# ti-tmds62levm-rev-b-sheet-17.net
KiCad netlist of a schematic drawn in Altium Designer
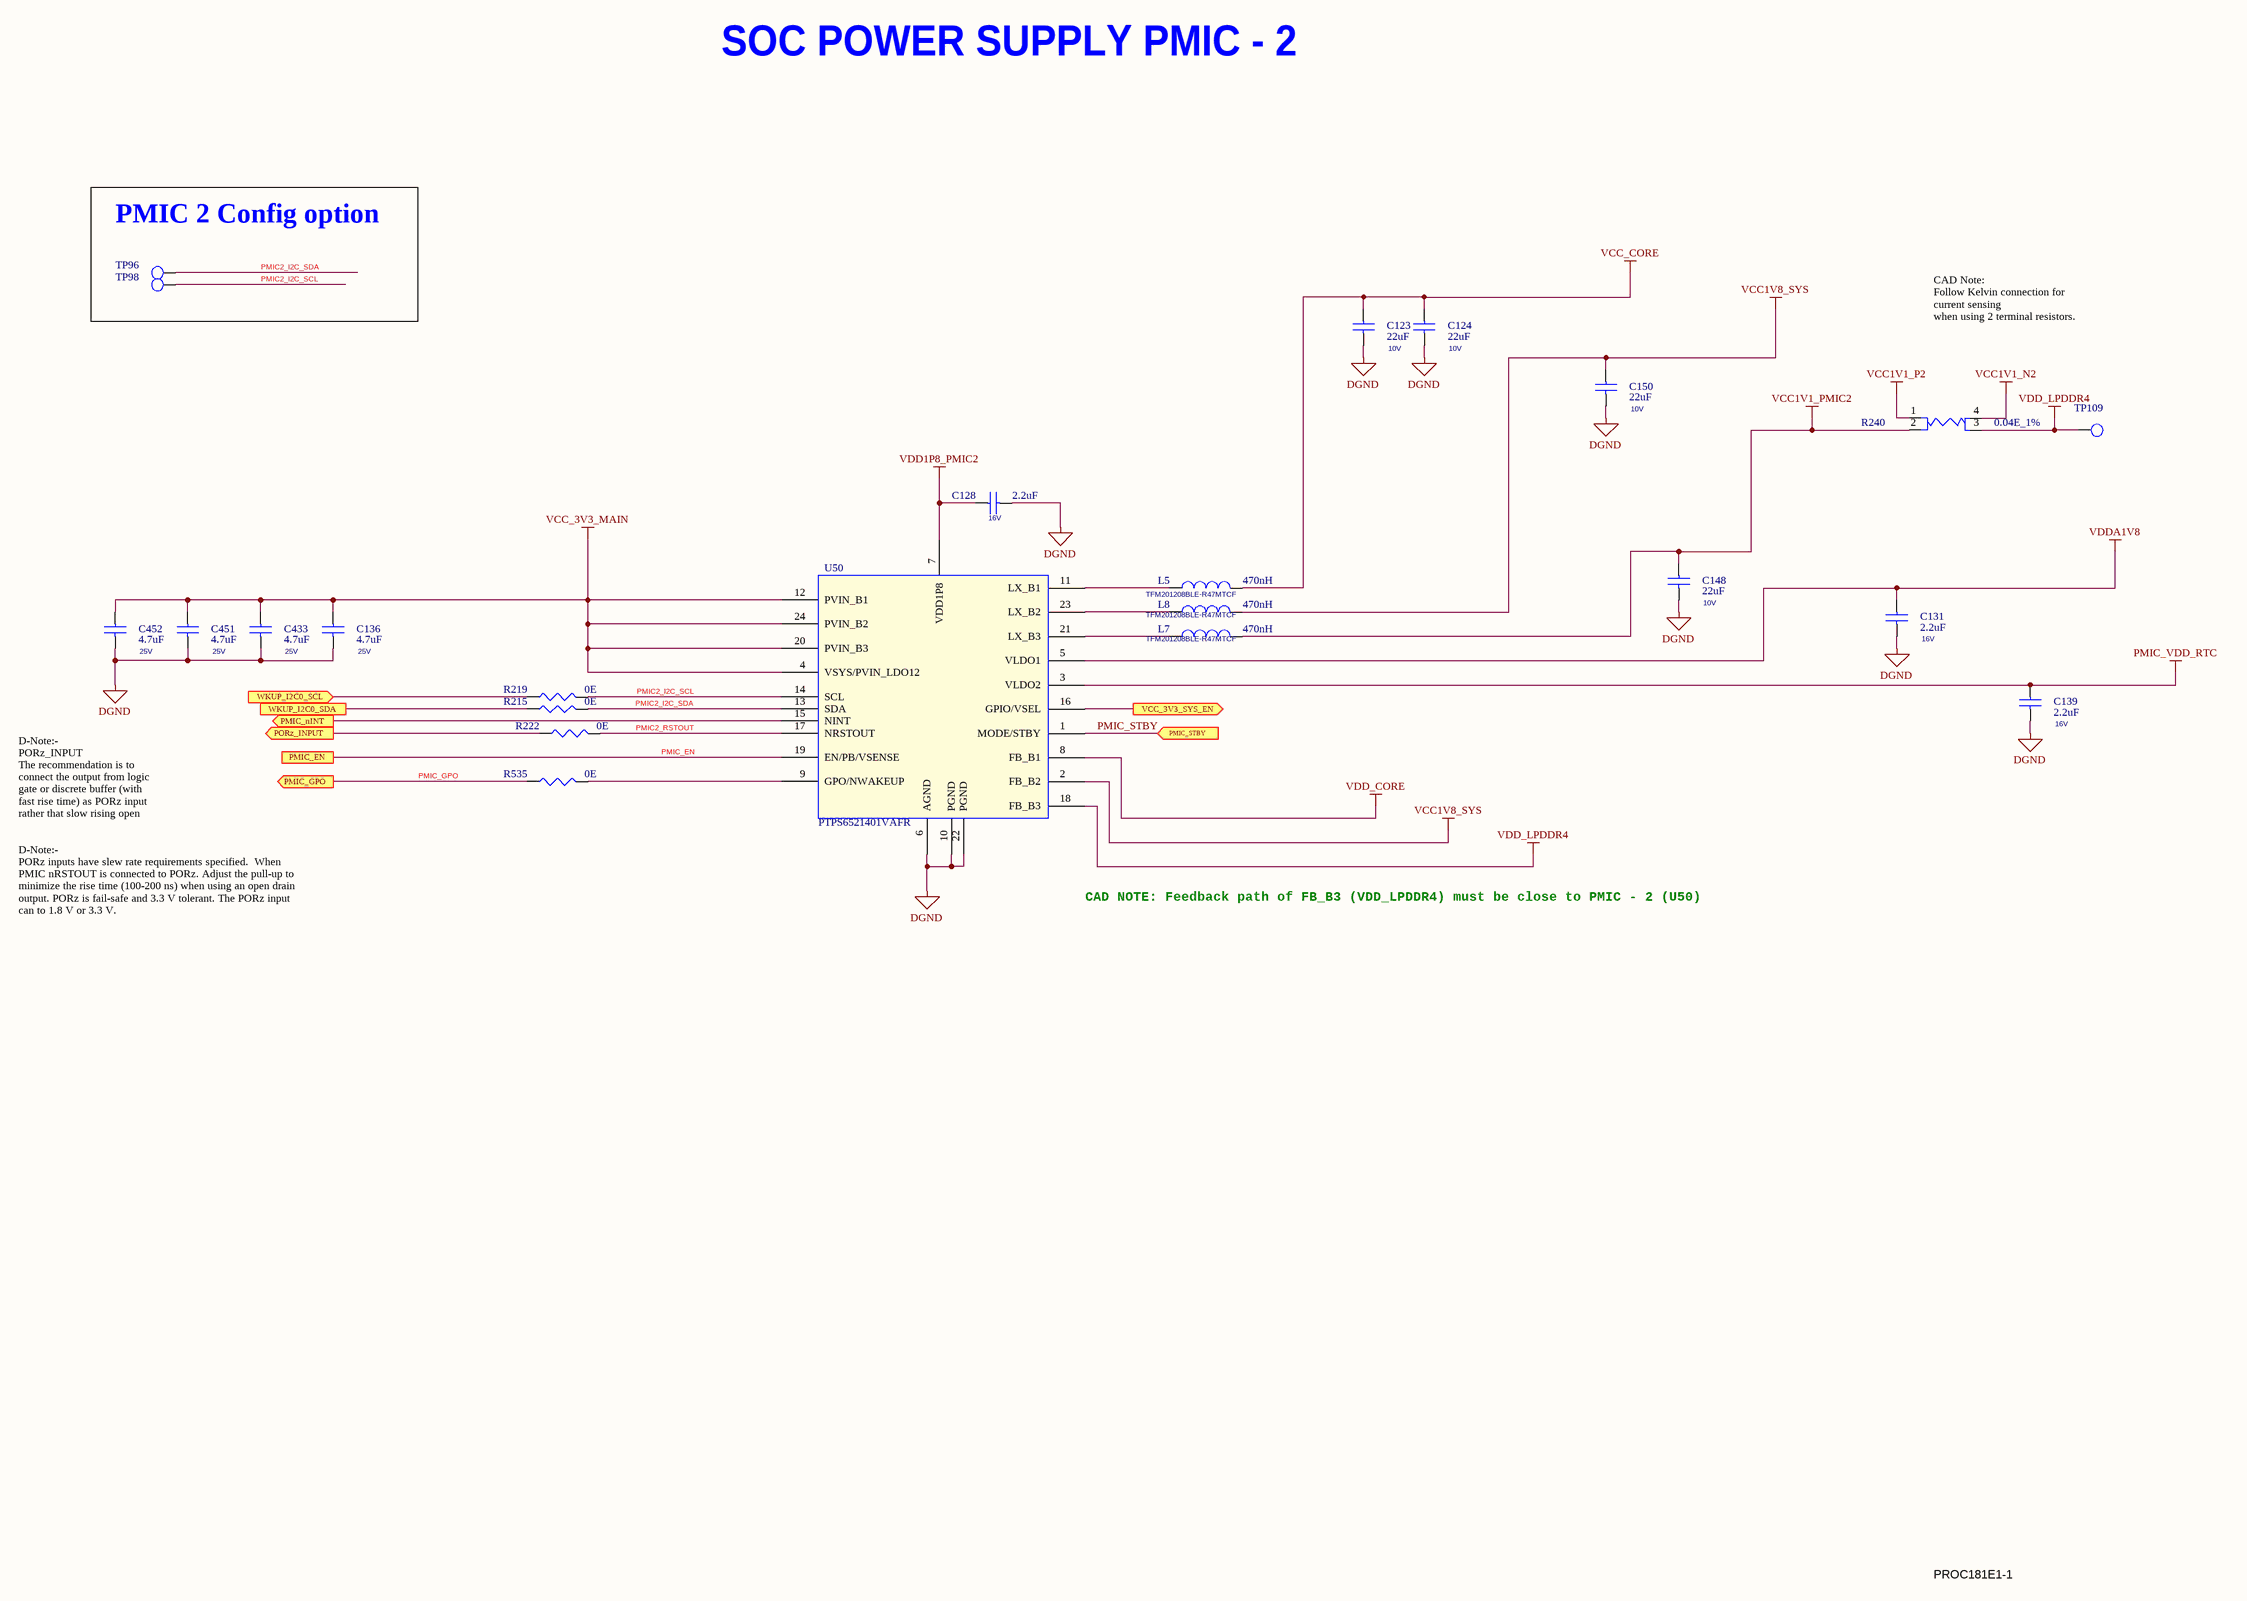
[diagram p0: ti-tmds62levm-rev-b-sheet-17.SchDoc]

(export (version "E")
  (design (tool "Eeschema 10.0.6"))
  (components
    (comp (ref "C123")
      (value "22uF")
      (footprint "CAP0805_1-5")
      (description "CAP CERAMIC 22uF 10V 20% X7R 0805")
      (fields
        (field (name "DISTRIBUTOR_PART_NUMBER") "490-GRM21BZ71A226ME15LCT-ND")
        (field (name "VOLTAGE") "10V")
        (field (name "TOLERANCE") "20%")
        (field (name "LIBRARY PATH") "Y~{:}MIS_DATABAS~{E}Librar~{y}ALTIUM_TOO~{L}SCHEMATICS_PART~{S}MS_DISCRETE_Library.schlib")
      )
      (libsource (lib "*") (part "CAP_Dup1"))
    )
    (comp (ref "C124")
      (value "22uF")
      (footprint "CAP0805_1-5")
      (description "CAP CERAMIC 22uF 10V 20% X7R 0805")
      (fields
        (field (name "MISTRAL PART NO") "120024060041-R")
        (field (name "MFR_PART_NUMBER") "GRM21BZ71A226ME15L")
        (field (name "VOLTAGE") "10V")
        (field (name "LIBRARY PATH") "Y~{:}MIS_DATABAS~{E}Librar~{y}ALTIUM_TOO~{L}SCHEMATICS_PART~{S}MS_DISCRETE_Library.schlib")
      )
      (libsource (lib "*") (part "CAP_Dup1"))
    )
    (comp (ref "C128")
      (value "2.2uF")
      (footprint "CAP0402_0-75")
      (description "CAP CERAMIC 2.2uF 16V 10% X6S 0402")
      (fields
        (field (name "DISTRIBUTOR_PART_NUMBER") "490-14595-1-ND")
        (field (name "VOLTAGE") "16V")
        (field (name "TOLERANCE") "10%")
        (field (name "LIBRARY PATH") "Y~{:}MIS_DATABAS~{E}Librar~{y}ALTIUM_TOO~{L}SCHEMATICS_PART~{S}MS_DISCRETE_Library.schlib")
      )
      (libsource (lib "*") (part "CAP_Dup1"))
    )
    (comp (ref "C131")
      (value "2.2uF")
      (footprint "CAP0402_0-75")
      (description "CAP CERAMIC 2.2uF 16V 10% X6S 0402")
      (fields
        (field (name "DISTRIBUTOR_PART_NUMBER") "490-14595-1-ND")
        (field (name "VOLTAGE") "16V")
        (field (name "TOLERANCE") "10%")
        (field (name "LIBRARY PATH") "Y~{:}MIS_DATABAS~{E}Librar~{y}ALTIUM_TOO~{L}SCHEMATICS_PART~{S}MS_DISCRETE_Library.schlib")
      )
      (libsource (lib "*") (part "CAP_Dup1"))
    )
    (comp (ref "C136")
      (value "4.7uF")
      (footprint "CAP0603_1")
      (description "CAP CERAMIC 4.7uF 25V 10% X6S 0603")
      (fields
        (field (name "DISTRIBUTOR_PART_NUMBER") "490-7199-1-ND")
        (field (name "VOLTAGE") "25V")
        (field (name "TOLERANCE") "10%")
        (field (name "LIBRARY PATH") "Y~{:}MIS_DATABAS~{E}Librar~{y}ALTIUM_TOO~{L}SCHEMATICS_PART~{S}MS_DISCRETE_Library.schlib")
      )
      (libsource (lib "*") (part "CAP_Dup1"))
    )
    (comp (ref "C139")
      (value "2.2uF")
      (footprint "CAP0402_0-75")
      (description "CAP CERAMIC 2.2uF 16V 10% X6S 0402")
      (fields
        (field (name "DISTRIBUTOR_PART_NUMBER") "490-14595-1-ND")
        (field (name "VOLTAGE") "16V")
        (field (name "TOLERANCE") "10%")
        (field (name "LIBRARY PATH") "Y~{:}MIS_DATABAS~{E}Librar~{y}ALTIUM_TOO~{L}SCHEMATICS_PART~{S}MS_DISCRETE_Library.schlib")
      )
      (libsource (lib "*") (part "CAP_Dup1"))
    )
    (comp (ref "C148")
      (value "22uF")
      (footprint "CAP0805_1-5")
      (description "CAP CERAMIC 22uF 10V 20% X7R 0805")
      (fields
        (field (name "MISTRAL PART NO") "120024060041-R")
        (field (name "MFR_PART_NUMBER") "GRM21BZ71A226ME15L")
        (field (name "VOLTAGE") "10V")
        (field (name "LIBRARY PATH") "Y~{:}MIS_DATABAS~{E}Librar~{y}ALTIUM_TOO~{L}SCHEMATICS_PART~{S}MS_DISCRETE_Library.schlib")
      )
      (libsource (lib "*") (part "CAP_Dup1"))
    )
    (comp (ref "C150")
      (value "22uF")
      (footprint "CAP0805_1-5")
      (description "CAP CERAMIC 22uF 10V 20% X7R 0805")
      (fields
        (field (name "MISTRAL PART NO") "120024060041-R")
        (field (name "MFR_PART_NUMBER") "GRM21BZ71A226ME15L")
        (field (name "VOLTAGE") "10V")
        (field (name "LIBRARY PATH") "Y~{:}MIS_DATABAS~{E}Librar~{y}ALTIUM_TOO~{L}SCHEMATICS_PART~{S}MS_DISCRETE_Library.schlib")
      )
      (libsource (lib "*") (part "CAP_Dup1"))
    )
    (comp (ref "C433")
      (value "4.7uF")
      (footprint "CAP0603_1")
      (description "CAP CERAMIC 4.7uF 25V 10% X6S 0603")
      (fields
        (field (name "MISTRAL PART NO") "120018100056-R")
        (field (name "MFR_PART_NUMBER") "GRM188C81E475KE11D")
        (field (name "VOLTAGE") "25V")
        (field (name "LIBRARY PATH") "Y~{:}MIS_DATABAS~{E}Librar~{y}ALTIUM_TOO~{L}SCHEMATICS_PART~{S}MS_DISCRETE_Library.schlib")
      )
      (libsource (lib "*") (part "CAP_Dup1"))
    )
    (comp (ref "C451")
      (value "4.7uF")
      (footprint "CAP0603_1")
      (description "CAP CERAMIC 4.7uF 25V 10% X6S 0603")
      (fields
        (field (name "MISTRAL PART NO") "120018100056-R")
        (field (name "MFR_PART_NUMBER") "GRM188C81E475KE11D")
        (field (name "VOLTAGE") "25V")
        (field (name "LIBRARY PATH") "Y~{:}MIS_DATABAS~{E}Librar~{y}ALTIUM_TOO~{L}SCHEMATICS_PART~{S}MS_DISCRETE_Library.schlib")
      )
      (libsource (lib "*") (part "CAP_Dup1"))
    )
    (comp (ref "C452")
      (value "4.7uF")
      (footprint "CAP0603_1")
      (description "CAP CERAMIC 4.7uF 25V 10% X6S 0603")
      (fields
        (field (name "DISTRIBUTOR_PART_NUMBER") "490-7199-1-ND")
        (field (name "VOLTAGE") "25V")
        (field (name "TOLERANCE") "10%")
        (field (name "LIBRARY PATH") "Y~{:}MIS_DATABAS~{E}Librar~{y}ALTIUM_TOO~{L}SCHEMATICS_PART~{S}MS_DISCRETE_Library.schlib")
      )
      (libsource (lib "*") (part "CAP_Dup1"))
    )
    (comp (ref "L5")
      (value "470nH")
      (footprint "IND_0805HT_90X60_SMD")
      (description "IND POWER 470nH 4A 20% 0805")
      (fields
        (field (name "DISTRIBUTOR_PART_NUMBER") "445-TFM201208BLE-R47MTCFCT-ND")
        (field (name "VOLTAGE") "NA")
        (field (name "MFR_PART_NUMBER") "TFM201208BLE-R47MTCF")
        (field (name "LIBRARY PATH") "Y~{:}MIS_DATABAS~{E}Librar~{y}ALTIUM_TOO~{L}SCHEMATICS_PART~{S}MS_DISCRETE_Library.schlib")
      )
      (libsource (lib "*") (part "INDUCTOR_Dup1"))
    )
    (comp (ref "L7")
      (value "470nH")
      (footprint "IND_0805HT_90X60_SMD")
      (description "IND POWER 470nH 4A 20% 0805")
      (fields
        (field (name "MISTRAL PART NO") "130024060053-R")
        (field (name "MFR_PART_NUMBER") "TFM201208BLE-R47MTCF")
        (field (name "TOLERANCE") "20%")
        (field (name "LIBRARY PATH") "Y~{:}MIS_DATABAS~{E}Librar~{y}ALTIUM_TOO~{L}SCHEMATICS_PART~{S}MS_DISCRETE_Library.schlib")
      )
      (libsource (lib "*") (part "INDUCTOR_Dup1"))
    )
    (comp (ref "L8")
      (value "470nH")
      (footprint "IND_0805HT_90X60_SMD")
      (description "IND POWER 470nH 4A 20% 0805")
      (fields
        (field (name "MISTRAL PART NO") "130024060053-R")
        (field (name "MFR_PART_NUMBER") "TFM201208BLE-R47MTCF")
        (field (name "TOLERANCE") "20%")
        (field (name "LIBRARY PATH") "Y~{:}MIS_DATABAS~{E}Librar~{y}ALTIUM_TOO~{L}SCHEMATICS_PART~{S}MS_DISCRETE_Library.schlib")
      )
      (libsource (lib "*") (part "INDUCTOR_Dup1"))
    )
    (comp (ref "R215")
      (value "0E")
      (footprint "RES0201_0-5")
      (description "RES 0E 1/20W 5% 0201")
      (fields
        (field (name "MISTRAL PART NO") "110010070067-R")
        (field (name "MFR_PART_NUMBER") "RC0201JR-070RL")
        (field (name "LIBRARY PATH") "Y~{:}MIS_DATABAS~{E}Librar~{y}ALTIUM_TOO~{L}SCHEMATICS_PART~{S}MS_DISCRETE_Library.schlib")
      )
      (libsource (lib "*") (part "RESISTOR_Dup4"))
    )
    (comp (ref "R219")
      (value "0E")
      (footprint "RES0201_0-5")
      (description "RES 0E 1/20W 5% 0201")
      (fields
        (field (name "MISTRAL PART NO") "110010070067-R")
        (field (name "MFR_PART_NUMBER") "RC0201JR-070RL")
        (field (name "LIBRARY PATH") "Y~{:}MIS_DATABAS~{E}Librar~{y}ALTIUM_TOO~{L}SCHEMATICS_PART~{S}MS_DISCRETE_Library.schlib")
      )
      (libsource (lib "*") (part "RESISTOR_Dup4"))
    )
    (comp (ref "R222")
      (value "0E")
      (footprint "RES0201_0-5")
      (description "RES 0E 1/20W 5% 0201")
      (fields
        (field (name "MISTRAL PART NO") "110010070067-R")
        (field (name "MFR_PART_NUMBER") "RC0201JR-070RL")
        (field (name "LIBRARY PATH") "Y~{:}MIS_DATABAS~{E}Librar~{y}ALTIUM_TOO~{L}SCHEMATICS_PART~{S}MS_DISCRETE_Library.schlib")
      )
      (libsource (lib "*") (part "RESISTOR_Dup4"))
    )
    (comp (ref "R240")
      (value "0.04E_1%")
      (footprint "RES_FC4T_1206-4_1")
      (description "RES CURRENT SENSE 0.04E 1/4W 1% 1206-4")
      (fields
        (field (name "DISTRIBUTOR_PART_NUMBER") "541-WSK1206R0400FEACT-ND")
        (field (name "VOLTAGE") "NA")
        (field (name "LIBRARY PATH") "Y~{:}MIS_DATABAS~{E}Librar~{y}ALTIUM_TOO~{L}SCHEMATICS_PART~{S}MS_DISCRETE_Library.schlib")
      )
      (libsource (lib "*") (part "RESISTOR-4TERM"))
    )
    (comp (ref "R535")
      (value "0E")
      (footprint "RES0201_0-5")
      (description "RES 0E 1/20W 5% 0201")
      (fields
        (field (name "MISTRAL PART NO") "110010070067-R")
        (field (name "MFR_PART_NUMBER") "RC0201JR-070RL")
        (field (name "LIBRARY PATH") "Y~{:}MIS_DATABAS~{E}Librar~{y}ALTIUM_TOO~{L}SCHEMATICS_PART~{S}MS_DISCRETE_Library.schlib")
      )
      (libsource (lib "*") (part "RESISTOR_Dup4"))
    )
    (comp (ref "TP96")
      (value "TP30_SMD")
      (footprint "TP30_SMD")
      (description "TESTPOINT CIR 30 SMD")
      (fields
        (field (name "MISTRAL PART NO") "130009030930")
        (field (name "TOLERANCE") "NA")
        (field (name "LIBRARY PATH") "Y~{:}MIS_DATABAS~{E}Librar~{y}ALTIUM_TOO~{L}SCHEMATICS_PART~{S}MS_DISCRETE_Library.schlib")
      )
      (libsource (lib "*") (part "TESTPOINT"))
    )
    (comp (ref "TP98")
      (value "TP30_SMD")
      (footprint "TP30_SMD")
      (description "TESTPOINT CIR 30 SMD")
      (fields
        (field (name "DISTRIBUTOR_PART_NUMBER") "NA")
        (field (name "MISTRAL PART NO") "130009030930")
        (field (name "LIBRARY PATH") "Y~{:}MIS_DATABAS~{E}Librar~{y}ALTIUM_TOO~{L}SCHEMATICS_PART~{S}MS_DISCRETE_Library.schlib")
      )
      (libsource (lib "*") (part "TESTPOINT"))
    )
    (comp (ref "TP109")
      (value "TP40_SMD")
      (footprint "TP40_SMD")
      (description "TESTPOINT CIR 40 SMD")
      (fields
        (field (name "DISTRIBUTOR_PART_NUMBER") "NA")
        (field (name "MISTRAL PART NO") "130009030933")
        (field (name "LIBRARY PATH") "Y~{:}MIS_DATABAS~{E}Librar~{y}ALTIUM_TOO~{L}SCHEMATICS_PART~{S}MS_DISCRETE_Library.schlib")
      )
      (libsource (lib "*") (part "TESTPOINT"))
    )
    (comp (ref "U50")
      (value "PTPS6521401VAFR")
      (footprint "WQFN24_PTPS6521401VAFR_140X140_0-8")
      (description "IC 4 INTEGRATED POWER MANAGEMENT FOR ARM CORTEX LOW POWER PROCESSORS AND FPGAS QFN24")
      (fields (field (name "DISTRIBUTOR_PART_NUMBER") "NA") (field (name "MISTRAL PART NO") "142024010015-R"))
      (libsource (lib "*") (part "TPS65214_QFN24"))
    )
  )
  (nets
    (net (code "1") (name "/PMIC2_I2C_SCL") (class "Default")
      (node (ref "R219") (pin "2") (pinfunction "2_2") (pintype "passive"))
      (node (ref "TP98") (pin "1") (pinfunction "TP_1") (pintype "passive"))
      (node (ref "U50") (pin "14") (pinfunction "SCL_14") (pintype "passive"))
    )
    (net (code "2") (name "/PMIC2_I2C_SDA") (class "Default")
      (node (ref "R215") (pin "2") (pinfunction "2_2") (pintype "passive"))
      (node (ref "TP96") (pin "1") (pinfunction "TP_1") (pintype "passive"))
      (node (ref "U50") (pin "13") (pinfunction "SDA_13") (pintype "passive"))
    )
    (net (code "3") (name "/PMIC2_RSTOUT") (class "Default")
      (node (ref "R222") (pin "2") (pinfunction "2_2") (pintype "passive"))
      (node (ref "U50") (pin "17") (pinfunction "NRSTOUT_17") (pintype "passive"))
    )
    (net (code "4") (name "/PMIC_EN") (class "Default")
      (node (ref "U50") (pin "19") (pinfunction "EN/PB/VSENSE_19") (pintype "passive"))
    )
    (net (code "5") (name "/PMIC_GPO") (class "Default")
      (node (ref "R535") (pin "1") (pinfunction "1_1") (pintype "passive"))
    )
    (net (code "6") (name "/PMIC_STBY") (class "Default")
      (node (ref "U50") (pin "1") (pinfunction "MODE/STBY_1") (pintype "passive"))
    )
    (net (code "7") (name "/PMIC_nINT") (class "Default")
      (node (ref "U50") (pin "15") (pinfunction "NINT_15") (pintype "passive"))
    )
    (net (code "8") (name "/PORz_INPUT") (class "Default")
      (node (ref "R222") (pin "1") (pinfunction "1_1") (pintype "passive"))
    )
    (net (code "9") (name "/VCC_3V3_SYS_EN") (class "Default")
      (node (ref "U50") (pin "16") (pinfunction "GPIO/VSEL_16") (pintype "passive"))
    )
    (net (code "10") (name "/WKUP_I2C0_SCL") (class "Default")
      (node (ref "R219") (pin "1") (pinfunction "1_1") (pintype "passive"))
    )
    (net (code "11") (name "/WKUP_I2C0_SDA") (class "Default")
      (node (ref "R215") (pin "1") (pinfunction "1_1") (pintype "passive"))
    )
    (net (code "12") (name "DGND") (class "Default")
      (node (ref "C123") (pin "2") (pinfunction "2_2") (pintype "passive"))
      (node (ref "C124") (pin "2") (pinfunction "2_2") (pintype "passive"))
      (node (ref "C128") (pin "2") (pinfunction "2_2") (pintype "passive"))
      (node (ref "C131") (pin "2") (pinfunction "2_2") (pintype "passive"))
      (node (ref "C136") (pin "2") (pinfunction "2_2") (pintype "passive"))
      (node (ref "C139") (pin "2") (pinfunction "2_2") (pintype "passive"))
      (node (ref "C148") (pin "2") (pinfunction "2_2") (pintype "passive"))
      (node (ref "C150") (pin "2") (pinfunction "2_2") (pintype "passive"))
      (node (ref "C433") (pin "2") (pinfunction "2_2") (pintype "passive"))
      (node (ref "C451") (pin "2") (pinfunction "2_2") (pintype "passive"))
      (node (ref "C452") (pin "2") (pinfunction "2_2") (pintype "passive"))
      (node (ref "U50") (pin "10") (pinfunction "PGND_10") (pintype "power_in"))
      (node (ref "U50") (pin "22") (pinfunction "PGND_22") (pintype "power_in"))
      (node (ref "U50") (pin "6") (pinfunction "AGND_6") (pintype "power_in"))
    )
    (net (code "13") (name "Net-(U50-GPO{slash}NWAKEUP)") (class "Default")
      (node (ref "R535") (pin "2") (pinfunction "2_2") (pintype "passive"))
      (node (ref "U50") (pin "9") (pinfunction "GPO/NWAKEUP_9") (pintype "passive"))
    )
    (net (code "14") (name "Net-(U50-LX_B1)") (class "Default")
      (node (ref "L5") (pin "1") (pinfunction "1_1") (pintype "passive"))
      (node (ref "U50") (pin "11") (pinfunction "LX_B1_11") (pintype "passive"))
    )
    (net (code "15") (name "Net-(U50-LX_B2)") (class "Default")
      (node (ref "L8") (pin "1") (pinfunction "1_1") (pintype "passive"))
      (node (ref "U50") (pin "23") (pinfunction "LX_B2_23") (pintype "passive"))
    )
    (net (code "16") (name "Net-(U50-LX_B3)") (class "Default")
      (node (ref "L7") (pin "1") (pinfunction "1_1") (pintype "passive"))
      (node (ref "U50") (pin "21") (pinfunction "LX_B3_21") (pintype "passive"))
    )
    (net (code "17") (name "PMIC_VDD_RTC") (class "Default")
      (node (ref "C139") (pin "1") (pinfunction "1_1") (pintype "passive"))
      (node (ref "U50") (pin "3") (pinfunction "VLDO2_3") (pintype "power_in"))
    )
    (net (code "18") (name "VCC1V1_N2") (class "Default")
      (node (ref "R240") (pin "4") (pinfunction "4_4") (pintype "passive"))
    )
    (net (code "19") (name "VCC1V1_P2") (class "Default")
      (node (ref "R240") (pin "1") (pinfunction "1_1") (pintype "passive"))
    )
    (net (code "20") (name "VCC1V1_PMIC2") (class "Default")
      (node (ref "C148") (pin "1") (pinfunction "1_1") (pintype "passive"))
      (node (ref "L7") (pin "2") (pinfunction "2_2") (pintype "passive"))
      (node (ref "R240") (pin "2") (pinfunction "2_2") (pintype "passive"))
    )
    (net (code "21") (name "VCC1V8_SYS") (class "Default")
      (node (ref "C150") (pin "1") (pinfunction "1_1") (pintype "passive"))
      (node (ref "L8") (pin "2") (pinfunction "2_2") (pintype "passive"))
      (node (ref "U50") (pin "2") (pinfunction "FB_B2_2") (pintype "passive"))
    )
    (net (code "22") (name "VCC_3V3_MAIN") (class "Default")
      (node (ref "C136") (pin "1") (pinfunction "1_1") (pintype "passive"))
      (node (ref "C433") (pin "1") (pinfunction "1_1") (pintype "passive"))
      (node (ref "C451") (pin "1") (pinfunction "1_1") (pintype "passive"))
      (node (ref "C452") (pin "1") (pinfunction "1_1") (pintype "passive"))
      (node (ref "U50") (pin "12") (pinfunction "PVIN_B1_12") (pintype "power_in"))
      (node (ref "U50") (pin "20") (pinfunction "PVIN_B3_20") (pintype "power_in"))
      (node (ref "U50") (pin "24") (pinfunction "PVIN_B2_24") (pintype "power_in"))
      (node (ref "U50") (pin "4") (pinfunction "VSYS/PVIN_LDO12_4") (pintype "power_in"))
    )
    (net (code "23") (name "VCC_CORE") (class "Default")
      (node (ref "C123") (pin "1") (pinfunction "1_1") (pintype "passive"))
      (node (ref "C124") (pin "1") (pinfunction "1_1") (pintype "passive"))
      (node (ref "L5") (pin "2") (pinfunction "2_2") (pintype "passive"))
    )
    (net (code "24") (name "VDD1P8_PMIC2") (class "Default")
      (node (ref "C128") (pin "1") (pinfunction "1_1") (pintype "passive"))
      (node (ref "U50") (pin "7") (pinfunction "VDD1P8_7") (pintype "power_in"))
    )
    (net (code "25") (name "VDDA1V8") (class "Default")
      (node (ref "C131") (pin "1") (pinfunction "1_1") (pintype "passive"))
      (node (ref "U50") (pin "5") (pinfunction "VLDO1_5") (pintype "power_in"))
    )
    (net (code "26") (name "VDD_CORE") (class "Default")
      (node (ref "U50") (pin "8") (pinfunction "FB_B1_8") (pintype "passive"))
    )
    (net (code "27") (name "VDD_LPDDR4") (class "Default")
      (node (ref "R240") (pin "3") (pinfunction "3_3") (pintype "passive"))
      (node (ref "TP109") (pin "1") (pinfunction "TP_1") (pintype "passive"))
      (node (ref "U50") (pin "18") (pinfunction "FB_B3_18") (pintype "passive"))
    )
  )
)
